# leds.net
KiCad netlist of a schematic drawn in EAGLE
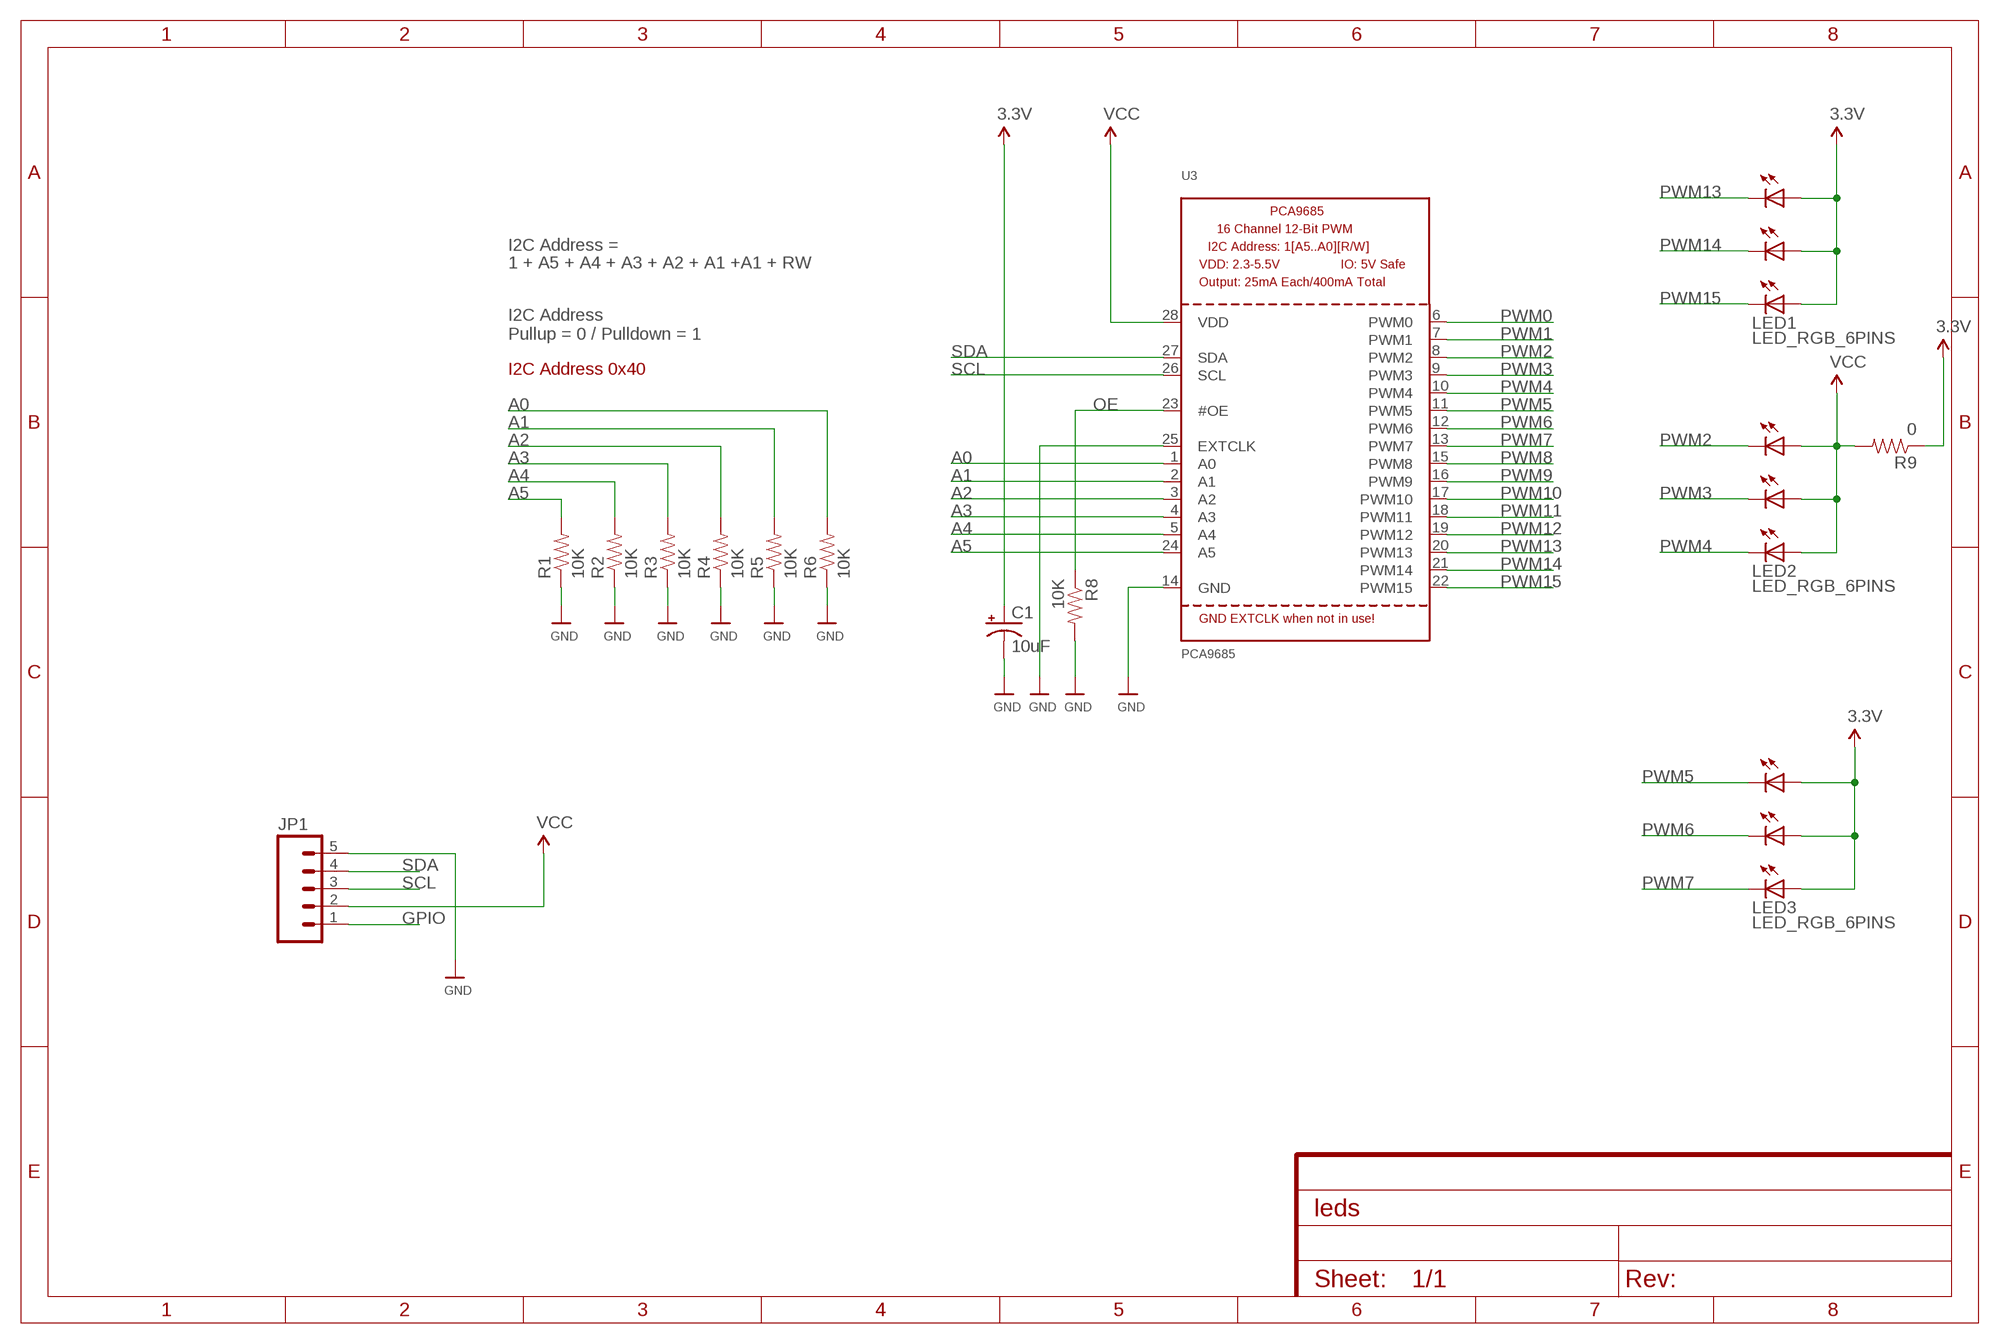
[diagram p0: schematic, sheet 1]

(export (version "E")
  (design (tool "Eeschema 10.0.6"))
  (components
    (comp (ref "C1")
      (value "10uF")
      (footprint "eagle-import:EIA3216")
      (libsource (lib "eagle-import") (part "CAP_POL1206"))
    )
    (comp (ref "JP1")
      (value "M05PTH")
      (footprint "eagle-import:1X05")
      (libsource (lib "eagle-import") (part "M05PTH"))
    )
    (comp (ref "LED1")
      (value "LED_RGB_6PINS")
      (footprint "eagle-import:LED_RGB_6PINS")
      (libsource (lib "eagle-import") (part "LED_RGB_6PINS"))
    )
    (comp (ref "LED2")
      (value "LED_RGB_6PINS")
      (footprint "eagle-import:LED_RGB_6PINS")
      (libsource (lib "eagle-import") (part "LED_RGB_6PINS"))
    )
    (comp (ref "LED3")
      (value "LED_RGB_6PINS")
      (footprint "eagle-import:LED_RGB_6PINS")
      (libsource (lib "eagle-import") (part "LED_RGB_6PINS"))
    )
    (comp (ref "R1")
      (value "10K")
      (footprint "eagle-import:1206")
      (libsource (lib "eagle-import") (part "SparkFun-Resistors_RESISTOR1206"))
    )
    (comp (ref "R2")
      (value "10K")
      (footprint "eagle-import:1206")
      (libsource (lib "eagle-import") (part "SparkFun-Resistors_RESISTOR1206"))
    )
    (comp (ref "R3")
      (value "10K")
      (footprint "eagle-import:1206")
      (libsource (lib "eagle-import") (part "SparkFun-Resistors_RESISTOR1206"))
    )
    (comp (ref "R4")
      (value "10K")
      (footprint "eagle-import:1206")
      (libsource (lib "eagle-import") (part "SparkFun-Resistors_RESISTOR1206"))
    )
    (comp (ref "R5")
      (value "10K")
      (footprint "eagle-import:1206")
      (libsource (lib "eagle-import") (part "SparkFun-Resistors_RESISTOR1206"))
    )
    (comp (ref "R6")
      (value "10K")
      (footprint "eagle-import:1206")
      (libsource (lib "eagle-import") (part "SparkFun-Resistors_RESISTOR1206"))
    )
    (comp (ref "R8")
      (value "10K")
      (footprint "eagle-import:1206")
      (libsource (lib "eagle-import") (part "SparkFun-Resistors_RESISTOR1206"))
    )
    (comp (ref "R9")
      (value "0")
      (footprint "eagle-import:R2512")
      (libsource (lib "eagle-import") (part "RESISTOR2512"))
    )
    (comp (ref "U3")
      (value "PCA9685")
      (footprint "eagle-import:TSSOP28")
      (libsource (lib "eagle-import") (part "PCA9685"))
    )
  )
  (nets
    (net (code "1") (name "/A0") (class "Default")
      (node (ref "R6") (pin "2") (pinfunction "2_2") (pintype "passive"))
      (node (ref "U3") (pin "1") (pinfunction "A0_1") (pintype "bidirectional"))
    )
    (net (code "2") (name "/A1") (class "Default")
      (node (ref "R5") (pin "2") (pinfunction "2_2") (pintype "passive"))
      (node (ref "U3") (pin "2") (pinfunction "A1_2") (pintype "bidirectional"))
    )
    (net (code "3") (name "/A2") (class "Default")
      (node (ref "R4") (pin "2") (pinfunction "2_2") (pintype "passive"))
      (node (ref "U3") (pin "3") (pinfunction "A2_3") (pintype "bidirectional"))
    )
    (net (code "4") (name "/A3") (class "Default")
      (node (ref "R3") (pin "2") (pinfunction "2_2") (pintype "passive"))
      (node (ref "U3") (pin "4") (pinfunction "A3_4") (pintype "bidirectional"))
    )
    (net (code "5") (name "/A4") (class "Default")
      (node (ref "R2") (pin "2") (pinfunction "2_2") (pintype "passive"))
      (node (ref "U3") (pin "5") (pinfunction "A4_5") (pintype "bidirectional"))
    )
    (net (code "6") (name "/A5") (class "Default")
      (node (ref "R1") (pin "2") (pinfunction "2_2") (pintype "passive"))
      (node (ref "U3") (pin "24") (pinfunction "A5_24") (pintype "bidirectional"))
    )
    (net (code "7") (name "/GPIO") (class "Default")
      (node (ref "JP1") (pin "1") (pinfunction "1_1") (pintype "passive"))
    )
    (net (code "8") (name "/OE") (class "Default")
      (node (ref "R8") (pin "1") (pinfunction "1_1") (pintype "passive"))
      (node (ref "U3") (pin "23") (pinfunction "#OE_23") (pintype "input"))
    )
    (net (code "9") (name "/PWM0") (class "Default")
      (node (ref "U3") (pin "6") (pinfunction "PWM0_6") (pintype "output"))
    )
    (net (code "10") (name "/PWM1") (class "Default")
      (node (ref "U3") (pin "7") (pinfunction "PWM1_7") (pintype "output"))
    )
    (net (code "11") (name "/PWM2") (class "Default")
      (node (ref "LED2") (pin "BC") (pinfunction "BC_BC") (pintype "passive"))
      (node (ref "U3") (pin "8") (pinfunction "PWM2_8") (pintype "output"))
    )
    (net (code "12") (name "/PWM3") (class "Default")
      (node (ref "LED2") (pin "RC") (pinfunction "RC_RC") (pintype "passive"))
      (node (ref "U3") (pin "9") (pinfunction "PWM3_9") (pintype "output"))
    )
    (net (code "13") (name "/PWM4") (class "Default")
      (node (ref "LED2") (pin "GC") (pinfunction "GC_GC") (pintype "passive"))
      (node (ref "U3") (pin "10") (pinfunction "PWM4_10") (pintype "output"))
    )
    (net (code "14") (name "/PWM5") (class "Default")
      (node (ref "LED3") (pin "BC") (pinfunction "BC_BC") (pintype "passive"))
      (node (ref "U3") (pin "11") (pinfunction "PWM5_11") (pintype "output"))
    )
    (net (code "15") (name "/PWM6") (class "Default")
      (node (ref "LED3") (pin "RC") (pinfunction "RC_RC") (pintype "passive"))
      (node (ref "U3") (pin "12") (pinfunction "PWM6_12") (pintype "output"))
    )
    (net (code "16") (name "/PWM7") (class "Default")
      (node (ref "LED3") (pin "GC") (pinfunction "GC_GC") (pintype "passive"))
      (node (ref "U3") (pin "13") (pinfunction "PWM7_13") (pintype "output"))
    )
    (net (code "17") (name "/PWM8") (class "Default")
      (node (ref "U3") (pin "15") (pinfunction "PWM8_15") (pintype "output"))
    )
    (net (code "18") (name "/PWM9") (class "Default")
      (node (ref "U3") (pin "16") (pinfunction "PWM9_16") (pintype "output"))
    )
    (net (code "19") (name "/PWM10") (class "Default")
      (node (ref "U3") (pin "17") (pinfunction "PWM10_17") (pintype "output"))
    )
    (net (code "20") (name "/PWM11") (class "Default")
      (node (ref "U3") (pin "18") (pinfunction "PWM11_18") (pintype "output"))
    )
    (net (code "21") (name "/PWM12") (class "Default")
      (node (ref "U3") (pin "19") (pinfunction "PWM12_19") (pintype "output"))
    )
    (net (code "22") (name "/PWM13") (class "Default")
      (node (ref "LED1") (pin "BC") (pinfunction "BC_BC") (pintype "passive"))
      (node (ref "U3") (pin "20") (pinfunction "PWM13_20") (pintype "output"))
    )
    (net (code "23") (name "/PWM14") (class "Default")
      (node (ref "LED1") (pin "RC") (pinfunction "RC_RC") (pintype "passive"))
      (node (ref "U3") (pin "21") (pinfunction "PWM14_21") (pintype "output"))
    )
    (net (code "24") (name "/PWM15") (class "Default")
      (node (ref "LED1") (pin "GC") (pinfunction "GC_GC") (pintype "passive"))
      (node (ref "U3") (pin "22") (pinfunction "PWM15_22") (pintype "output"))
    )
    (net (code "25") (name "/SCL") (class "Default")
      (node (ref "JP1") (pin "3") (pinfunction "3_3") (pintype "passive"))
      (node (ref "U3") (pin "26") (pinfunction "SCL_26") (pintype "bidirectional"))
    )
    (net (code "26") (name "/SDA") (class "Default")
      (node (ref "JP1") (pin "4") (pinfunction "4_4") (pintype "passive"))
      (node (ref "U3") (pin "27") (pinfunction "SDA_27") (pintype "bidirectional"))
    )
    (net (code "27") (name "3.3V") (class "Default")
      (node (ref "C1") (pin "A") (pinfunction "+_A") (pintype "passive"))
      (node (ref "LED1") (pin "BA") (pinfunction "BA_BA") (pintype "passive"))
      (node (ref "LED1") (pin "GA") (pinfunction "GA_GA") (pintype "passive"))
      (node (ref "LED1") (pin "RA") (pinfunction "RA_RA") (pintype "passive"))
      (node (ref "LED3") (pin "BA") (pinfunction "BA_BA") (pintype "passive"))
      (node (ref "LED3") (pin "GA") (pinfunction "GA_GA") (pintype "passive"))
      (node (ref "LED3") (pin "RA") (pinfunction "RA_RA") (pintype "passive"))
      (node (ref "R9") (pin "1") (pinfunction "1_1") (pintype "passive"))
    )
    (net (code "28") (name "GND") (class "Default")
      (node (ref "C1") (pin "C") (pinfunction "-_C") (pintype "passive"))
      (node (ref "JP1") (pin "5") (pinfunction "5_5") (pintype "passive"))
      (node (ref "R1") (pin "1") (pinfunction "1_1") (pintype "passive"))
      (node (ref "R2") (pin "1") (pinfunction "1_1") (pintype "passive"))
      (node (ref "R3") (pin "1") (pinfunction "1_1") (pintype "passive"))
      (node (ref "R4") (pin "1") (pinfunction "1_1") (pintype "passive"))
      (node (ref "R5") (pin "1") (pinfunction "1_1") (pintype "passive"))
      (node (ref "R6") (pin "1") (pinfunction "1_1") (pintype "passive"))
      (node (ref "R8") (pin "2") (pinfunction "2_2") (pintype "passive"))
      (node (ref "U3") (pin "14") (pinfunction "GND_14") (pintype "power_in"))
      (node (ref "U3") (pin "25") (pinfunction "EXTCLK_25") (pintype "input"))
    )
    (net (code "29") (name "VCC") (class "Default")
      (node (ref "JP1") (pin "2") (pinfunction "2_2") (pintype "passive"))
      (node (ref "LED2") (pin "BA") (pinfunction "BA_BA") (pintype "passive"))
      (node (ref "LED2") (pin "GA") (pinfunction "GA_GA") (pintype "passive"))
      (node (ref "LED2") (pin "RA") (pinfunction "RA_RA") (pintype "passive"))
      (node (ref "R9") (pin "2") (pinfunction "2_2") (pintype "passive"))
      (node (ref "U3") (pin "28") (pinfunction "VDD_28") (pintype "power_in"))
    )
  )
)
